# 010_SoC_RGMII_GBE_PHY.net
KiCad netlist of a schematic drawn in Altium Designer
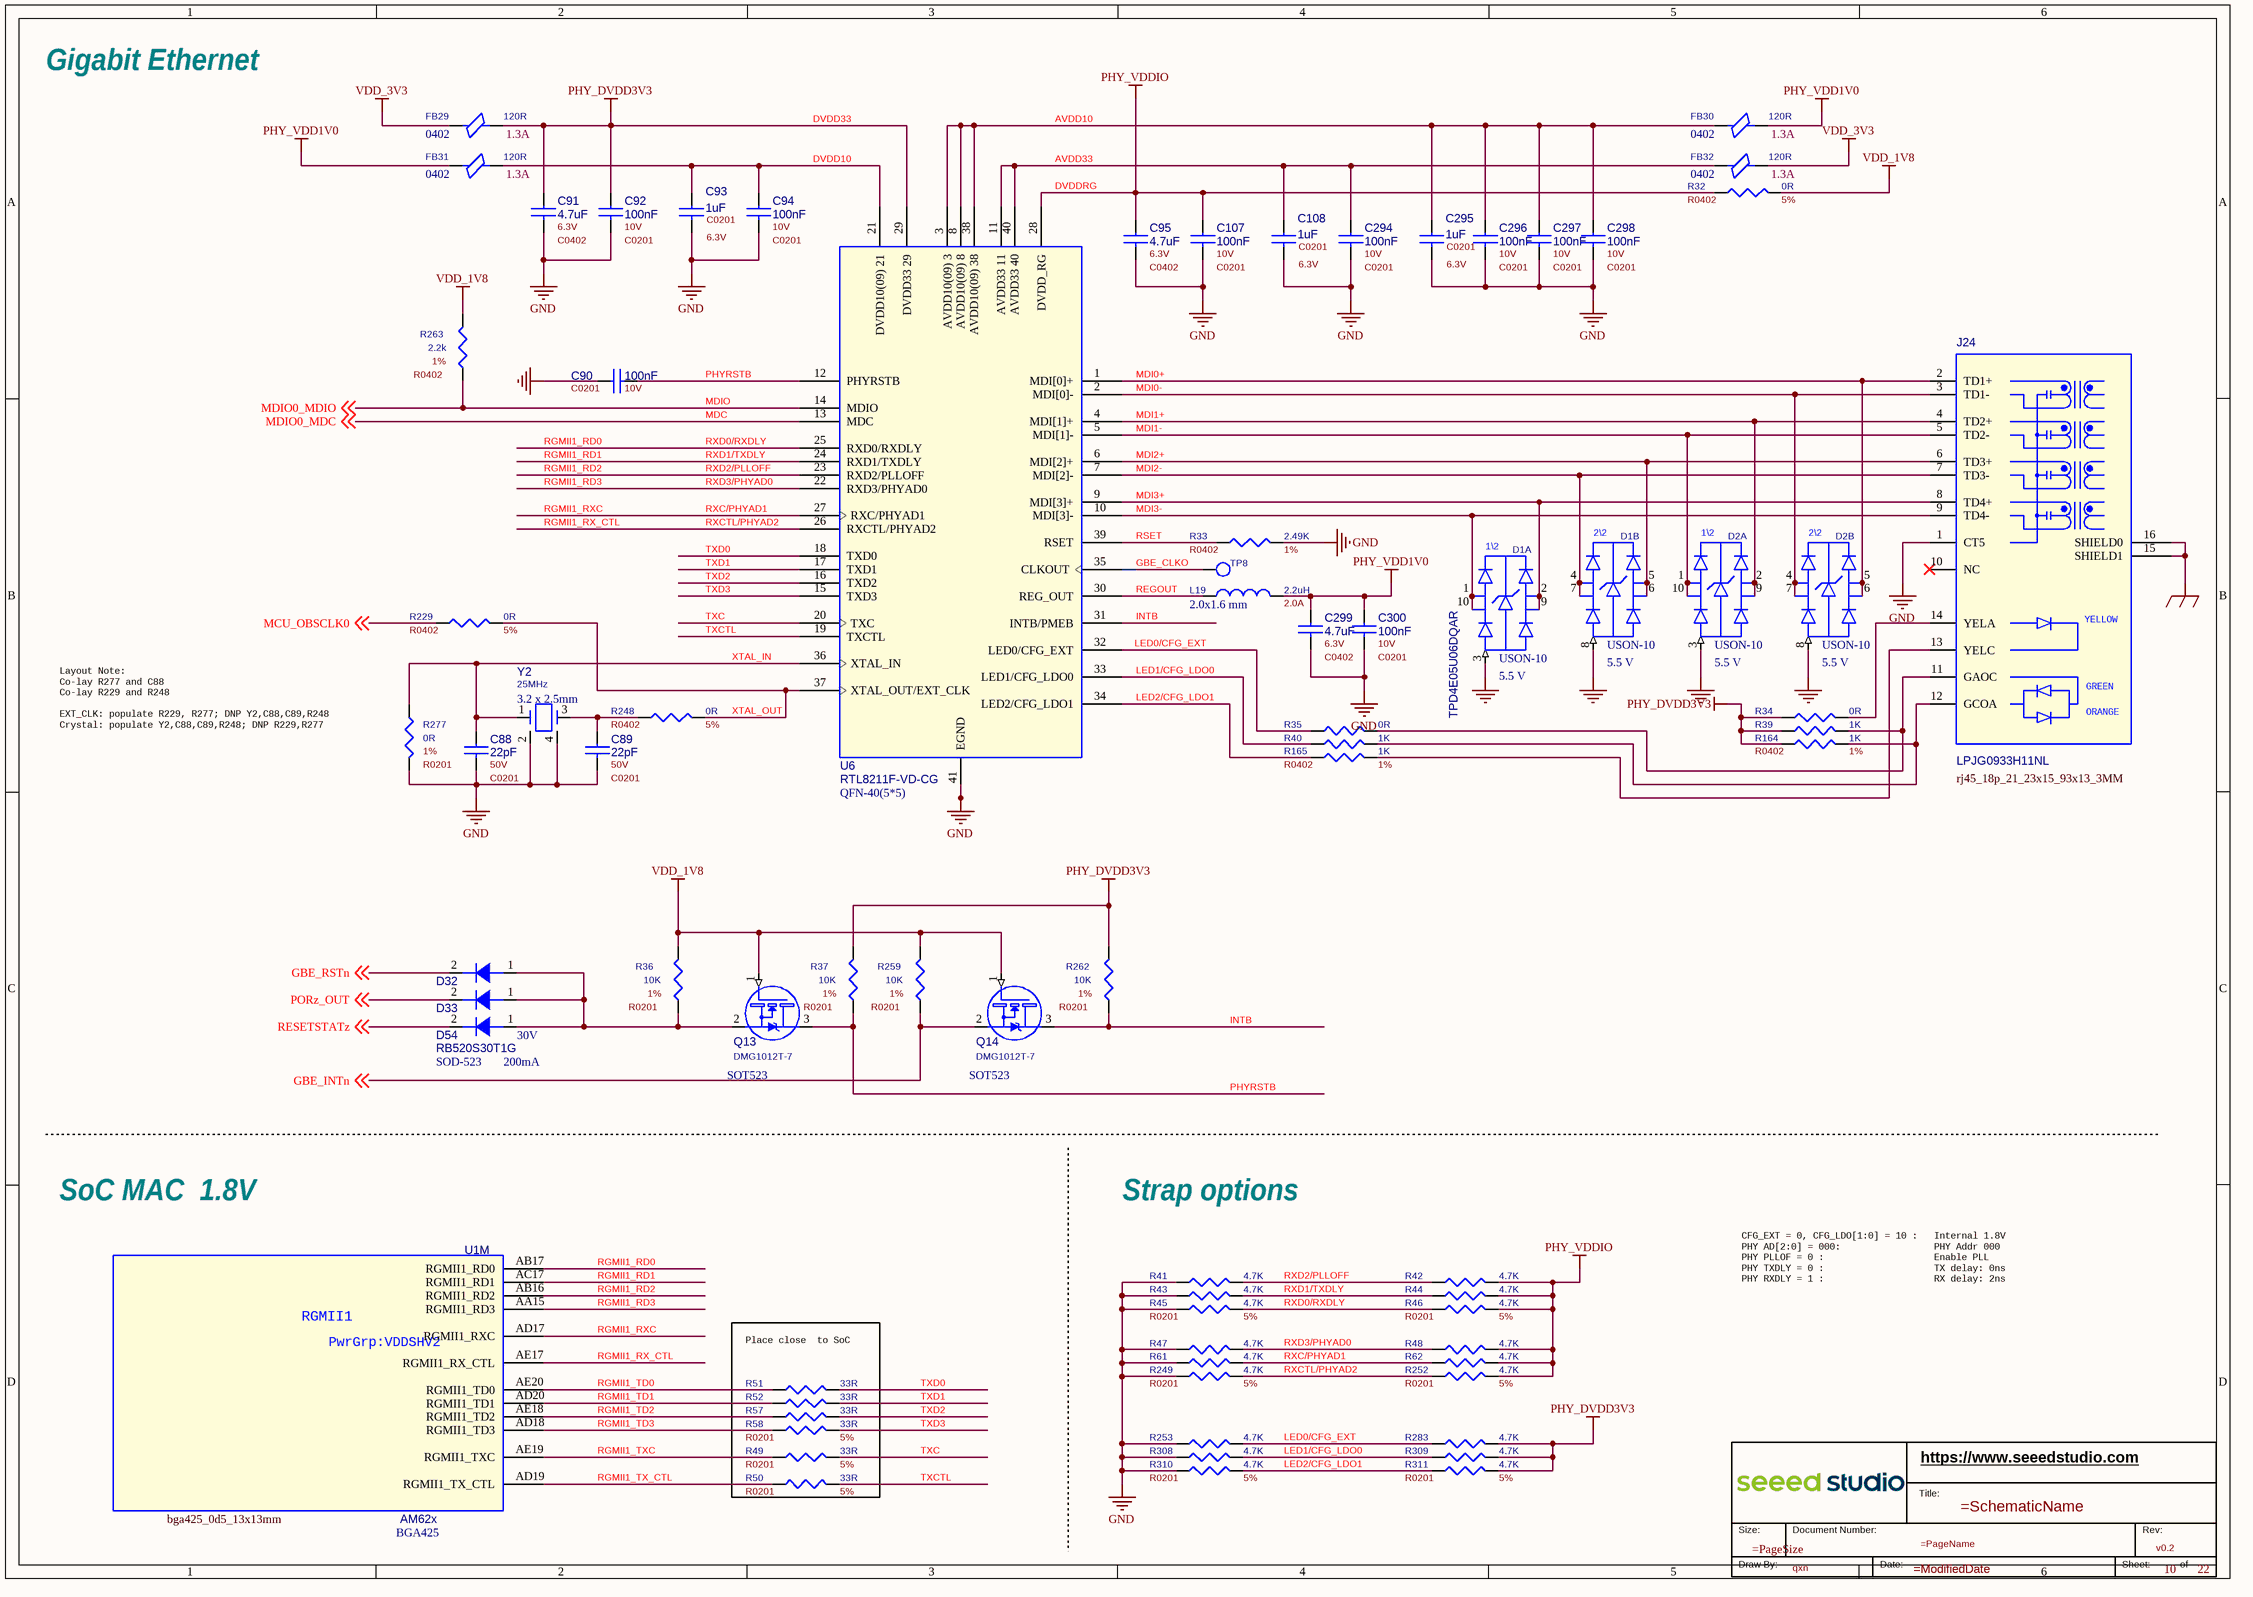
[diagram p0: 010_SoC RGMII & GBE PHY.SchDoc]

(export (version "E")
  (design (tool "Eeschema 10.0.6"))
  (components
    (comp (ref "C88")
      (value "22pF")
      (footprint "C0201")
      (description "CAP, Ceramic, SMD, 22pF, 5%, 50V, 0201")
      (fields
        (field (name "RATING") "50V")
        (field (name "PCB FOOTPRINT") "C0201")
        (field (name "TOLERANCE") "5%")
        (field (name "MANUFACTURER") "YAGEO")
      )
      (libsource (lib "*") (part "CC"))
    )
    (comp (ref "C89")
      (value "22pF")
      (footprint "C0201")
      (description "CAP, Ceramic, SMD, 22pF, 5%, 50V, 0201")
      (fields
        (field (name "RATING") "50V")
        (field (name "PCB FOOTPRINT") "C0201")
        (field (name "MANUFACTURER") "YAGEO")
        (field (name "TOLERANCE") "5%")
      )
      (libsource (lib "*") (part "CC"))
    )
    (comp (ref "C90")
      (value "100nF")
      (footprint "C0201")
      (description "CAP, Ceramic, SMD, 100nF, 10%, 10V, 0201")
      (fields
        (field (name "RATING") "10V")
        (field (name "PCB FOOTPRINT") "C0201")
        (field (name "MANUFACTURER") "YAGEO")
        (field (name "TOLERANCE") "10%")
      )
      (libsource (lib "") (part "CC_1"))
    )
    (comp (ref "C91")
      (value "4.7uF")
      (footprint "C0402")
      (description "CAP, Ceramic, SMD, 4.7uF, 20%, 6.3V, 0402")
      (fields
        (field (name "RATING") "6.3V")
        (field (name "PCB FOOTPRINT") "C0402")
        (field (name "TOLERANCE") "20%")
        (field (name "MANUFACTURER") "YAGEO")
      )
      (libsource (lib "*") (part "CC"))
    )
    (comp (ref "C92")
      (value "100nF")
      (footprint "C0201")
      (description "CAP, Ceramic, SMD, 100nF, 10%, 10V, 0201")
      (fields
        (field (name "RATING") "10V")
        (field (name "PCB FOOTPRINT") "C0201")
        (field (name "MANUFACTURER") "YAGEO")
        (field (name "TOLERANCE") "10%")
      )
      (libsource (lib "*") (part "CC"))
    )
    (comp (ref "C93")
      (value "1uF")
      (footprint "C0201")
      (description "CAP, Ceramic, SMD, 1uF, 20%, 6.3V, 0201")
      (fields
        (field (name "RATING") "6.3V")
        (field (name "PCB FOOTPRINT") "C0201")
        (field (name "TOLERANCE") "20%")
        (field (name "MANUFACTURER") "YAGEO")
      )
      (libsource (lib "*") (part "CC"))
    )
    (comp (ref "C94")
      (value "100nF")
      (footprint "C0201")
      (description "CAP, Ceramic, SMD, 100nF, 10%, 10V, 0201")
      (fields
        (field (name "RATING") "10V")
        (field (name "PCB FOOTPRINT") "C0201")
        (field (name "TOLERANCE") "10%")
        (field (name "MANUFACTURER") "YAGEO")
      )
      (libsource (lib "*") (part "CC"))
    )
    (comp (ref "C95")
      (value "4.7uF")
      (footprint "C0402")
      (description "CAP, Ceramic, SMD, 4.7uF, 20%, 6.3V, 0402")
      (fields
        (field (name "RATING") "6.3V")
        (field (name "PCB FOOTPRINT") "C0402")
        (field (name "TOLERANCE") "20%")
        (field (name "MANUFACTURER") "YAGEO")
      )
      (libsource (lib "*") (part "CC"))
    )
    (comp (ref "C107")
      (value "100nF")
      (footprint "C0201")
      (description "CAP, Ceramic, SMD, 100nF, 10%, 10V, 0201")
      (fields
        (field (name "RATING") "10V")
        (field (name "PCB FOOTPRINT") "C0201")
        (field (name "MANUFACTURER") "YAGEO")
        (field (name "TOLERANCE") "10%")
      )
      (libsource (lib "*") (part "CC"))
    )
    (comp (ref "C108")
      (value "1uF")
      (footprint "C0201")
      (description "CAP, Ceramic, SMD, 1uF, 20%, 6.3V, 0201")
      (fields
        (field (name "RATING") "6.3V")
        (field (name "PCB FOOTPRINT") "C0201")
        (field (name "MANUFACTURER") "YAGEO")
        (field (name "TOLERANCE") "20%")
      )
      (libsource (lib "*") (part "CC"))
    )
    (comp (ref "C294")
      (value "100nF")
      (footprint "C0201")
      (description "CAP, Ceramic, SMD, 100nF, 10%, 10V, 0201")
      (fields
        (field (name "RATING") "10V")
        (field (name "PCB FOOTPRINT") "C0201")
        (field (name "MANUFACTURER") "YAGEO")
        (field (name "TOLERANCE") "10%")
      )
      (libsource (lib "*") (part "CC"))
    )
    (comp (ref "C295")
      (value "1uF")
      (footprint "C0201")
      (description "CAP, Ceramic, SMD, 1uF, 20%, 6.3V, 0201")
      (fields
        (field (name "RATING") "6.3V")
        (field (name "PCB FOOTPRINT") "C0201")
        (field (name "MANUFACTURER") "YAGEO")
        (field (name "TOLERANCE") "20%")
      )
      (libsource (lib "*") (part "CC"))
    )
    (comp (ref "C296")
      (value "100nF")
      (footprint "C0201")
      (description "CAP, Ceramic, SMD, 100nF, 10%, 10V, 0201")
      (fields
        (field (name "RATING") "10V")
        (field (name "PCB FOOTPRINT") "C0201")
        (field (name "TOLERANCE") "10%")
        (field (name "MANUFACTURER") "YAGEO")
      )
      (libsource (lib "*") (part "CC"))
    )
    (comp (ref "C297")
      (value "100nF")
      (footprint "C0201")
      (description "CAP, Ceramic, SMD, 100nF, 10%, 10V, 0201")
      (fields
        (field (name "RATING") "10V")
        (field (name "PCB FOOTPRINT") "C0201")
        (field (name "TOLERANCE") "10%")
        (field (name "MANUFACTURER") "YAGEO")
      )
      (libsource (lib "*") (part "CC"))
    )
    (comp (ref "C298")
      (value "100nF")
      (footprint "C0201")
      (description "CAP, Ceramic, SMD, 100nF, 10%, 10V, 0201")
      (fields
        (field (name "RATING") "10V")
        (field (name "PCB FOOTPRINT") "C0201")
        (field (name "TOLERANCE") "10%")
        (field (name "MANUFACTURER") "YAGEO")
      )
      (libsource (lib "*") (part "CC"))
    )
    (comp (ref "C299")
      (value "4.7uF")
      (footprint "C0402")
      (description "CAP, Ceramic, SMD, 4.7uF, 20%, 6.3V, 0402")
      (fields
        (field (name "RATING") "6.3V")
        (field (name "PCB FOOTPRINT") "C0402")
        (field (name "MANUFACTURER") "YAGEO")
        (field (name "TOLERANCE") "20%")
      )
      (libsource (lib "*") (part "CC"))
    )
    (comp (ref "C300")
      (value "100nF")
      (footprint "C0201")
      (description "CAP, Ceramic, SMD, 100nF, 10%, 10V, 0201")
      (fields
        (field (name "RATING") "10V")
        (field (name "PCB FOOTPRINT") "C0201")
        (field (name "MANUFACTURER") "YAGEO")
        (field (name "TOLERANCE") "10%")
      )
      (libsource (lib "*") (part "CC"))
    )
    (comp (ref "D1")
      (value "D_ESD_DIFFPAIR")
      (footprint "uson10_0d5_2d5x1x0d5mm")
      (description "DIO, ESD, TPD4E05U06DQAR, --, 5.5 V, --, USON-10")
      (fields
        (field (name "PACKAGE SIZE") "USON-10")
        (field (name "RATED VOLTAGE") "5.5 V")
        (field (name "MANUFACTURER") "TI")
        (field (name "Comment") "D_ESD_DIFFPAIR")
      )
      (libsource (lib "*") (part "D_ESD_DIFFPAIR"))
    )
    (comp (ref "D2")
      (value "D_ESD_DIFFPAIR")
      (footprint "uson10_0d5_2d5x1x0d5mm")
      (description "DIO, ESD, TPD4E05U06DQAR, --, 5.5 V, --, USON-10")
      (fields
        (field (name "MANUFACTURER") "TI")
        (field (name "RATED VOLTAGE") "5.5 V")
        (field (name "PACKAGE SIZE") "USON-10")
      )
      (libsource (lib "*") (part "D_ESD_DIFFPAIR"))
    )
    (comp (ref "D32")
      (value "D")
      (footprint "sod_523")
      (description "DIO, Schottky, RB520S30T1G, , , , SOD-523")
      (fields (field (name "MANUFACTURER") "ON"))
      (libsource (lib "*") (part "D"))
    )
    (comp (ref "D33")
      (value "D")
      (footprint "sod_523")
      (description "DIO, Schottky, RB520S30T1G, , , , SOD-523")
      (fields (field (name "MANUFACTURER") "ON"))
      (libsource (lib "*") (part "D"))
    )
    (comp (ref "D54")
      (value "RB520S30T1G")
      (footprint "sod_523")
      (description "DIO, Schottky, RB520S30T1G, , , , SOD-523")
      (fields
        (field (name "MANUFACTURER") "ON")
        (field (name "REPETITIVE REVERSE VOLTAGE MAXIMUM") "30V")
        (field (name "PEAK FORWARD CURRENT") "200mA")
        (field (name "PACKAGE SIZE") "SOD-523")
        (field (name "Comment") "D")
      )
      (libsource (lib "*") (part "D"))
    )
    (comp (ref "FB29")
      (value "120R")
      (footprint "L0402")
      (description "Ferrite Bead, 120R, , 1.3A, 0402")
      (fields
        (field (name "RATING") "1.3A")
        (field (name "PACKAGE SIZE") "0402")
        (field (name "MANUFACTURER") "Murata")
        (field (name "Comment") "FB")
      )
      (libsource (lib "*") (part "FB"))
    )
    (comp (ref "FB30")
      (value "120R")
      (footprint "L0402")
      (description "Ferrite Bead, 120R, , 1.3A, 0402")
      (fields
        (field (name "RATING") "1.3A")
        (field (name "MANUFACTURER") "Murata")
        (field (name "PACKAGE SIZE") "0402")
        (field (name "Comment") "FB")
      )
      (libsource (lib "*") (part "FB"))
    )
    (comp (ref "FB31")
      (value "120R")
      (footprint "L0402")
      (description "Ferrite Bead, 120R, , 1.3A, 0402")
      (fields
        (field (name "RATING") "1.3A")
        (field (name "MANUFACTURER") "Murata")
        (field (name "PACKAGE SIZE") "0402")
        (field (name "Comment") "FB")
      )
      (libsource (lib "*") (part "FB"))
    )
    (comp (ref "FB32")
      (value "120R")
      (footprint "L0402")
      (description "Ferrite Bead, 120R, , 1.3A, 0402")
      (fields
        (field (name "RATING") "1.3A")
        (field (name "PACKAGE SIZE") "0402")
        (field (name "MANUFACTURER") "Murata")
        (field (name "Comment") "FB")
      )
      (libsource (lib "*") (part "FB"))
    )
    (comp (ref "J24")
      (value "LPJG0933H11NL")
      (footprint "rj45_18p_21_23x15_93x13_3MM")
      (description "CONN, RJ45, LPJG0933H11NL, 16P, DIP")
      (fields
        (field (name "PCB FOOTPRINT") "rj45_18p_21_23x15_93x13_3MM")
        (field (name "MANUFACTURER") "LINK-PP")
        (field (name "Comment") "RJ45_LPJG0933H11NL")
      )
      (libsource (lib "*") (part "RJ45_LPJG0933H11NL"))
    )
    (comp (ref "L19")
      (value "2.2uH")
      (footprint "L2016")
      (description "Power Inductor, 2.2uH, 20%, 2.0A, 2.0x1.6 mm")
      (fields
        (field (name "RATING") "2.0A")
        (field (name "MANUFACTURER") "CODACA")
        (field (name "PACKAGE SIZE") "2.0x1.6 mm")
        (field (name "Comment") "L")
      )
      (libsource (lib "*") (part "L"))
    )
    (comp (ref "Q13")
      (value "DMG1012T-7")
      (footprint "SOT_523")
      (description "XSTR, MOSFET, N-Channel, DMG1012T-7, 20V, 630mA, SOT523, SMD")
      (fields
        (field (name "PACKAGE SIZE") "SOT523")
        (field (name "MANUFACTURER") "Diodes")
        (field (name "Comment") "NMOS_123")
      )
      (libsource (lib "*") (part "NMOS_123"))
    )
    (comp (ref "Q14")
      (value "DMG1012T-7")
      (footprint "SOT_523")
      (description "XSTR, MOSFET, N-Channel, DMG1012T-7, 20V, 630mA, SOT523, SMD")
      (fields
        (field (name "PACKAGE SIZE") "SOT523")
        (field (name "MANUFACTURER") "Diodes")
        (field (name "Comment") "NMOS_123")
      )
      (libsource (lib "*") (part "NMOS_123"))
    )
    (comp (ref "R32")
      (value "0R")
      (footprint "R0402")
      (description "RES, Thick Film, 0R, 5%, 1/16W, SMD, 0402")
      (fields
        (field (name "RATING") "5%")
        (field (name "PCB FOOTPRINT") "R0402")
        (field (name "MANUFACTURER") "YAGEO")
        (field (name "Comment") "R")
      )
      (libsource (lib "*") (part "R"))
    )
    (comp (ref "R33")
      (value "2.49K")
      (footprint "R0402")
      (description "RES, Thick Film, 2.49K, 1%, 1/16W, SMD, 0402")
      (fields
        (field (name "RATING") "1%")
        (field (name "PCB FOOTPRINT") "R0402")
        (field (name "MANUFACTURER") "YAGEO")
        (field (name "Comment") "R")
      )
      (libsource (lib "*") (part "R"))
    )
    (comp (ref "R34")
      (value "0R")
      (footprint "R0402")
      (description "RES, Thick Film, 0R, 5%, 1/16W, SMD, 0402")
      (fields (field (name "MANUFACTURER") "YAGEO") (field (name "Comment") "R"))
      (libsource (lib "*") (part "R"))
    )
    (comp (ref "R35")
      (value "0R")
      (footprint "R0402")
      (description "RES, Thick Film, 0R, 5%, 1/16W, SMD, 0402")
      (fields (field (name "MANUFACTURER") "YAGEO") (field (name "Comment") "R"))
      (libsource (lib "*") (part "R"))
    )
    (comp (ref "R36")
      (value "10K")
      (footprint "R0201")
      (description "RES, Thick Film, 10K, 1%, 1/20W, SMD, 0201")
      (fields
        (field (name "RATING") "1%")
        (field (name "PCB FOOTPRINT") "R0201")
        (field (name "MANUFACTURER") "YAGEO")
        (field (name "Comment") "R")
      )
      (libsource (lib "") (part "R_1"))
    )
    (comp (ref "R37")
      (value "10K")
      (footprint "R0201")
      (description "RES, Thick Film, 10K, 1%, 1/20W, SMD, 0201")
      (fields
        (field (name "RATING") "1%")
        (field (name "PCB FOOTPRINT") "R0201")
        (field (name "MANUFACTURER") "YAGEO")
        (field (name "Comment") "R")
      )
      (libsource (lib "") (part "R_1"))
    )
    (comp (ref "R39")
      (value "1K")
      (footprint "R0402")
      (description "RES, Thick Film, 1K, 1%, 1/16W, SMD, 0402")
      (fields (field (name "MANUFACTURER") "YAGEO") (field (name "Comment") "R"))
      (libsource (lib "*") (part "R"))
    )
    (comp (ref "R40")
      (value "1K")
      (footprint "R0402")
      (description "RES, Thick Film, 1K, 1%, 1/16W, SMD, 0402")
      (fields (field (name "MANUFACTURER") "YAGEO") (field (name "Comment") "R"))
      (libsource (lib "*") (part "R"))
    )
    (comp (ref "R41")
      (value "4.7K")
      (footprint "R0201")
      (description "RES, Thick Film, 4.7K, 5%, 1/20W, SMD, 0201")
      (fields (field (name "MANUFACTURER") "YAGEO") (field (name "Comment") "R"))
      (libsource (lib "*") (part "R"))
    )
    (comp (ref "R42")
      (value "4.7K")
      (footprint "R0201")
      (description "RES, Thick Film, 4.7K, 5%, 1/20W, SMD, 0201")
      (fields (field (name "MANUFACTURER") "YAGEO") (field (name "Comment") "R"))
      (libsource (lib "*") (part "R"))
    )
    (comp (ref "R43")
      (value "4.7K")
      (footprint "R0201")
      (description "RES, Thick Film, 4.7K, 5%, 1/20W, SMD, 0201")
      (fields (field (name "MANUFACTURER") "YAGEO") (field (name "Comment") "R"))
      (libsource (lib "*") (part "R"))
    )
    (comp (ref "R44")
      (value "4.7K")
      (footprint "R0201")
      (description "RES, Thick Film, 4.7K, 5%, 1/20W, SMD, 0201")
      (fields (field (name "MANUFACTURER") "YAGEO") (field (name "Comment") "R"))
      (libsource (lib "*") (part "R"))
    )
    (comp (ref "R45")
      (value "4.7K")
      (footprint "R0201")
      (description "RES, Thick Film, 4.7K, 5%, 1/20W, SMD, 0201")
      (fields
        (field (name "RATING") "5%")
        (field (name "PCB FOOTPRINT") "R0201")
        (field (name "MANUFACTURER") "YAGEO")
        (field (name "Comment") "R")
      )
      (libsource (lib "*") (part "R"))
    )
    (comp (ref "R46")
      (value "4.7K")
      (footprint "R0201")
      (description "RES, Thick Film, 4.7K, 5%, 1/20W, SMD, 0201")
      (fields
        (field (name "RATING") "5%")
        (field (name "PCB FOOTPRINT") "R0201")
        (field (name "MANUFACTURER") "YAGEO")
        (field (name "Comment") "R")
      )
      (libsource (lib "*") (part "R"))
    )
    (comp (ref "R47")
      (value "4.7K")
      (footprint "R0201")
      (description "RES, Thick Film, 4.7K, 5%, 1/20W, SMD, 0201")
      (fields (field (name "MANUFACTURER") "YAGEO") (field (name "Comment") "R"))
      (libsource (lib "*") (part "R"))
    )
    (comp (ref "R48")
      (value "4.7K")
      (footprint "R0201")
      (description "RES, Thick Film, 4.7K, 5%, 1/20W, SMD, 0201")
      (fields (field (name "MANUFACTURER") "YAGEO") (field (name "Comment") "R"))
      (libsource (lib "*") (part "R"))
    )
    (comp (ref "R49")
      (value "33R")
      (footprint "R0201")
      (description "RES, Thick Film, 33R, 5%, 1/20W, SMD, 0201")
      (fields
        (field (name "RATING") "5%")
        (field (name "PCB FOOTPRINT") "R0201")
        (field (name "MANUFACTURER") "YAGEO")
        (field (name "Comment") "R")
      )
      (libsource (lib "*") (part "R"))
    )
    (comp (ref "R50")
      (value "33R")
      (footprint "R0201")
      (description "RES, Thick Film, 33R, 5%, 1/20W, SMD, 0201")
      (fields
        (field (name "RATING") "5%")
        (field (name "PCB FOOTPRINT") "R0201")
        (field (name "MANUFACTURER") "YAGEO")
        (field (name "Comment") "R")
      )
      (libsource (lib "*") (part "R"))
    )
    (comp (ref "R51")
      (value "33R")
      (footprint "R0201")
      (description "RES, Thick Film, 33R, 5%, 1/20W, SMD, 0201")
      (fields (field (name "MANUFACTURER") "YAGEO") (field (name "Comment") "R"))
      (libsource (lib "*") (part "R"))
    )
    (comp (ref "R52")
      (value "33R")
      (footprint "R0201")
      (description "RES, Thick Film, 33R, 5%, 1/20W, SMD, 0201")
      (fields (field (name "MANUFACTURER") "YAGEO") (field (name "Comment") "R"))
      (libsource (lib "*") (part "R"))
    )
    (comp (ref "R57")
      (value "33R")
      (footprint "R0201")
      (description "RES, Thick Film, 33R, 5%, 1/20W, SMD, 0201")
      (fields (field (name "MANUFACTURER") "YAGEO") (field (name "Comment") "R"))
      (libsource (lib "*") (part "R"))
    )
    (comp (ref "R58")
      (value "33R")
      (footprint "R0201")
      (description "RES, Thick Film, 33R, 5%, 1/20W, SMD, 0201")
      (fields
        (field (name "RATING") "5%")
        (field (name "PCB FOOTPRINT") "R0201")
        (field (name "MANUFACTURER") "YAGEO")
        (field (name "Comment") "R")
      )
      (libsource (lib "*") (part "R"))
    )
    (comp (ref "R61")
      (value "4.7K")
      (footprint "R0201")
      (description "RES, Thick Film, 4.7K, 5%, 1/20W, SMD, 0201")
      (fields (field (name "MANUFACTURER") "YAGEO") (field (name "Comment") "R"))
      (libsource (lib "*") (part "R"))
    )
    (comp (ref "R62")
      (value "4.7K")
      (footprint "R0201")
      (description "RES, Thick Film, 4.7K, 5%, 1/20W, SMD, 0201")
      (fields (field (name "MANUFACTURER") "YAGEO") (field (name "Comment") "R"))
      (libsource (lib "*") (part "R"))
    )
    (comp (ref "R164")
      (value "1K")
      (footprint "R0402")
      (description "RES, Thick Film, 1K, 1%, 1/16W, SMD, 0402")
      (fields
        (field (name "RATING") "1%")
        (field (name "PCB FOOTPRINT") "R0402")
        (field (name "MANUFACTURER") "YAGEO")
        (field (name "Comment") "R")
      )
      (libsource (lib "*") (part "R"))
    )
    (comp (ref "R165")
      (value "1K")
      (footprint "R0402")
      (description "RES, Thick Film, 1K, 1%, 1/16W, SMD, 0402")
      (fields
        (field (name "RATING") "1%")
        (field (name "PCB FOOTPRINT") "R0402")
        (field (name "MANUFACTURER") "YAGEO")
        (field (name "Comment") "R")
      )
      (libsource (lib "*") (part "R"))
    )
    (comp (ref "R229")
      (value "0R")
      (footprint "R0402")
      (description "RES, Thick Film, 0R, 5%, 1/16W, SMD, 0402")
      (fields
        (field (name "RATING") "5%")
        (field (name "PCB FOOTPRINT") "R0402")
        (field (name "MANUFACTURER") "YAGEO")
        (field (name "Comment") "R")
      )
      (libsource (lib "*") (part "R"))
    )
    (comp (ref "R248")
      (value "0R")
      (footprint "R0402")
      (description "RES, Thick Film, 0R, 5%, 1/16W, SMD, 0402")
      (fields
        (field (name "RATING") "5%")
        (field (name "PCB FOOTPRINT") "R0402")
        (field (name "MANUFACTURER") "YAGEO")
        (field (name "Comment") "R")
      )
      (libsource (lib "*") (part "R"))
    )
    (comp (ref "R249")
      (value "4.7K")
      (footprint "R0201")
      (description "RES, Thick Film, 4.7K, 5%, 1/20W, SMD, 0201")
      (fields
        (field (name "RATING") "5%")
        (field (name "PCB FOOTPRINT") "R0201")
        (field (name "MANUFACTURER") "YAGEO")
        (field (name "Comment") "R")
      )
      (libsource (lib "*") (part "R"))
    )
    (comp (ref "R252")
      (value "4.7K")
      (footprint "R0201")
      (description "RES, Thick Film, 4.7K, 5%, 1/20W, SMD, 0201")
      (fields
        (field (name "RATING") "5%")
        (field (name "PCB FOOTPRINT") "R0201")
        (field (name "MANUFACTURER") "YAGEO")
        (field (name "Comment") "R")
      )
      (libsource (lib "*") (part "R"))
    )
    (comp (ref "R253")
      (value "4.7K")
      (footprint "R0201")
      (description "RES, Thick Film, 4.7K, 5%, 1/20W, SMD, 0201")
      (fields (field (name "MANUFACTURER") "YAGEO") (field (name "Comment") "R"))
      (libsource (lib "*") (part "R"))
    )
    (comp (ref "R259")
      (value "10K")
      (footprint "R0201")
      (description "RES, Thick Film, 10K, 1%, 1/20W, SMD, 0201")
      (fields
        (field (name "RATING") "1%")
        (field (name "PCB FOOTPRINT") "R0201")
        (field (name "MANUFACTURER") "YAGEO")
        (field (name "Comment") "R")
      )
      (libsource (lib "") (part "R_1"))
    )
    (comp (ref "R262")
      (value "10K")
      (footprint "R0201")
      (description "RES, Thick Film, 10K, 1%, 1/20W, SMD, 0201")
      (fields
        (field (name "RATING") "1%")
        (field (name "PCB FOOTPRINT") "R0201")
        (field (name "MANUFACTURER") "YAGEO")
        (field (name "Comment") "R")
      )
      (libsource (lib "") (part "R_1"))
    )
    (comp (ref "R263")
      (value "2.2k")
      (footprint "R0402")
      (description "RES, Thick Film, 2.2k, 1%, 1/16W, SMD, 0402")
      (fields
        (field (name "RATING") "1%")
        (field (name "PCB FOOTPRINT") "R0402")
        (field (name "MANUFACTURER") "YAGEO")
        (field (name "Comment") "R")
      )
      (libsource (lib "") (part "R_1"))
    )
    (comp (ref "R277")
      (value "0R")
      (footprint "R0201")
      (description "RES, Thick Film, 0R, 5%, 1/20W, SMD, 0201")
      (fields
        (field (name "RATING") "1%")
        (field (name "PCB FOOTPRINT") "R0201")
        (field (name "MANUFACTURER") "YAGEO")
        (field (name "Comment") "R")
      )
      (libsource (lib "") (part "R_1"))
    )
    (comp (ref "R283")
      (value "4.7K")
      (footprint "R0201")
      (description "RES, Thick Film, 4.7K, 5%, 1/20W, SMD, 0201")
      (fields (field (name "MANUFACTURER") "YAGEO") (field (name "Comment") "R"))
      (libsource (lib "*") (part "R"))
    )
    (comp (ref "R308")
      (value "4.7K")
      (footprint "R0201")
      (description "RES, Thick Film, 4.7K, 5%, 1/20W, SMD, 0201")
      (fields (field (name "MANUFACTURER") "YAGEO") (field (name "Comment") "R"))
      (libsource (lib "*") (part "R"))
    )
    (comp (ref "R309")
      (value "4.7K")
      (footprint "R0201")
      (description "RES, Thick Film, 4.7K, 5%, 1/20W, SMD, 0201")
      (fields (field (name "MANUFACTURER") "YAGEO") (field (name "Comment") "R"))
      (libsource (lib "*") (part "R"))
    )
    (comp (ref "R310")
      (value "4.7K")
      (footprint "R0201")
      (description "RES, Thick Film, 4.7K, 5%, 1/20W, SMD, 0201")
      (fields
        (field (name "RATING") "5%")
        (field (name "PCB FOOTPRINT") "R0201")
        (field (name "MANUFACTURER") "YAGEO")
        (field (name "Comment") "R")
      )
      (libsource (lib "*") (part "R"))
    )
    (comp (ref "R311")
      (value "4.7K")
      (footprint "R0201")
      (description "RES, Thick Film, 4.7K, 5%, 1/20W, SMD, 0201")
      (fields
        (field (name "RATING") "5%")
        (field (name "PCB FOOTPRINT") "R0201")
        (field (name "MANUFACTURER") "YAGEO")
        (field (name "Comment") "R")
      )
      (libsource (lib "*") (part "R"))
    )
    (comp (ref "TP8")
      (value "Test Point")
      (footprint "tp1-8040")
      (description "MISC, Test Point, Test Point, SMD, TP30C_SMD")
      (libsource (lib "*") (part "Test Point"))
    )
    (comp (ref "U1")
      (value "AM62x")
      (footprint "bga425_0d5_13x13mm")
      (description "IC, Controller, MPU, AM62x, BGA425")
      (fields
        (field (name "PCB FOOTPRINT") "bga425_0d5_13x13mm")
        (field (name "PACKAGE SIZE") "BGA425")
        (field (name "MANUFACTURER") "TI")
        (field (name "Comment") "AM62x_BGA425")
      )
      (libsource (lib "*") (part "AM62x_BGA425"))
    )
    (comp (ref "U6")
      (value "RTL8211F-VD-CG")
      (footprint "qfn40_0D4_5x5mm")
      (description "IC, Interface, Ethernet, RTL8211F-VD-CG, QFN-40(5*5)")
      (fields
        (field (name "MANUFACTURER") "Realtek")
        (field (name "PACKAGE SIZE") "QFN-40(5*5)")
        (field (name "Comment") "RTL8211")
      )
      (libsource (lib "*") (part "RTL8211"))
    )
    (comp (ref "Y2")
      (value "25MHz")
      (footprint "CRY-SMD4-CX101F")
      (description "Crystal, SMD, 25MHz, 20 ppm, 18pF")
      (fields
        (field (name "MANUFACTURER") "Interquip")
        (field (name "PACKAGE SIZE") "3.2 x 2.5mm")
        (field (name "Comment") "XTAL_4P_2")
      )
      (libsource (lib "*") (part "XTAL_4P_2"))
    )
  )
  (nets
    (net (code "1") (name "/AVDD10") (class "Default")
      (node (ref "C295") (pin "1") (pinfunction "1_1") (pintype "passive"))
      (node (ref "C296") (pin "1") (pinfunction "1_1") (pintype "passive"))
      (node (ref "C297") (pin "1") (pinfunction "1_1") (pintype "passive"))
      (node (ref "C298") (pin "1") (pinfunction "1_1") (pintype "passive"))
      (node (ref "FB30") (pin "1") (pinfunction "1_1") (pintype "passive"))
      (node (ref "U6") (pin "3") (pinfunction "AVDD10(09)_3_3") (pintype "power_in"))
      (node (ref "U6") (pin "38") (pinfunction "AVDD10(09)_38_38") (pintype "power_in"))
      (node (ref "U6") (pin "8") (pinfunction "AVDD10(09)_8_8") (pintype "power_in"))
    )
    (net (code "2") (name "/AVDD33") (class "Default")
      (node (ref "C108") (pin "1") (pinfunction "1_1") (pintype "passive"))
      (node (ref "C294") (pin "1") (pinfunction "1_1") (pintype "passive"))
      (node (ref "FB32") (pin "1") (pinfunction "1_1") (pintype "passive"))
      (node (ref "U6") (pin "11") (pinfunction "AVDD33_11_11") (pintype "power_in"))
      (node (ref "U6") (pin "40") (pinfunction "AVDD33_40_40") (pintype "power_in"))
    )
    (net (code "3") (name "/DVDD10") (class "Default")
      (node (ref "C93") (pin "1") (pinfunction "1_1") (pintype "passive"))
      (node (ref "C94") (pin "1") (pinfunction "1_1") (pintype "passive"))
      (node (ref "FB31") (pin "2") (pinfunction "2_2") (pintype "passive"))
      (node (ref "U6") (pin "21") (pinfunction "DVDD10(09)_21_21") (pintype "power_in"))
    )
    (net (code "4") (name "/GBE_CLKO") (class "Default")
      (node (ref "TP8") (pin "1") (pinfunction "TP_1") (pintype "passive"))
      (node (ref "U6") (pin "35") (pinfunction "CLKOUT_35") (pintype "passive"))
    )
    (net (code "5") (name "/INTB") (class "Default")
      (node (ref "Q14") (pin "3") (pinfunction "D_3") (pintype "passive"))
      (node (ref "R262") (pin "2") (pinfunction "2_2") (pintype "passive"))
      (node (ref "U6") (pin "31") (pinfunction "INTB/PMEB_31") (pintype "passive"))
    )
    (net (code "6") (name "/LED0{slash}CFG_EXT") (class "Default")
      (node (ref "R253") (pin "2") (pinfunction "2_2") (pintype "passive"))
      (node (ref "R283") (pin "1") (pinfunction "1_1") (pintype "passive"))
      (node (ref "R35") (pin "1") (pinfunction "1_1") (pintype "passive"))
      (node (ref "U6") (pin "32") (pinfunction "LED0/CFG_EXT_32") (pintype "passive"))
    )
    (net (code "7") (name "/LED1{slash}CFG_LDO0") (class "Default")
      (node (ref "R308") (pin "2") (pinfunction "2_2") (pintype "passive"))
      (node (ref "R309") (pin "1") (pinfunction "1_1") (pintype "passive"))
      (node (ref "R40") (pin "1") (pinfunction "1_1") (pintype "passive"))
      (node (ref "U6") (pin "33") (pinfunction "LED1/CFG_LDO0_33") (pintype "passive"))
    )
    (net (code "8") (name "/LED2{slash}CFG_LDO1") (class "Default")
      (node (ref "R165") (pin "1") (pinfunction "1_1") (pintype "passive"))
      (node (ref "R310") (pin "2") (pinfunction "2_2") (pintype "passive"))
      (node (ref "R311") (pin "1") (pinfunction "1_1") (pintype "passive"))
      (node (ref "U6") (pin "34") (pinfunction "LED2/CFG_LDO1_34") (pintype "passive"))
    )
    (net (code "9") (name "/MDI0+") (class "Default")
      (node (ref "D2") (pin "5") (pinfunction "4A_5") (pintype "passive"))
      (node (ref "D2") (pin "6") (pinfunction "4B_6") (pintype "passive"))
      (node (ref "J24") (pin "2") (pinfunction "TD1+_2") (pintype "passive"))
      (node (ref "U6") (pin "1") (pinfunction "MDI[0]+_1") (pintype "passive"))
    )
    (net (code "10") (name "/MDI0-") (class "Default")
      (node (ref "D2") (pin "4") (pinfunction "3A_4") (pintype "passive"))
      (node (ref "D2") (pin "7") (pinfunction "3B_7") (pintype "passive"))
      (node (ref "J24") (pin "3") (pinfunction "TD1-_3") (pintype "passive"))
      (node (ref "U6") (pin "2") (pinfunction "MDI[0]-_2") (pintype "passive"))
    )
    (net (code "11") (name "/MDI1+") (class "Default")
      (node (ref "D2") (pin "2") (pinfunction "2A_2") (pintype "passive"))
      (node (ref "D2") (pin "9") (pinfunction "2B_9") (pintype "passive"))
      (node (ref "J24") (pin "4") (pinfunction "TD2+_4") (pintype "passive"))
      (node (ref "U6") (pin "4") (pinfunction "MDI[1]+_4") (pintype "passive"))
    )
    (net (code "12") (name "/MDI1-") (class "Default")
      (node (ref "D2") (pin "1") (pinfunction "1A_1") (pintype "passive"))
      (node (ref "D2") (pin "10") (pinfunction "1B_10") (pintype "passive"))
      (node (ref "J24") (pin "5") (pinfunction "TD2-_5") (pintype "passive"))
      (node (ref "U6") (pin "5") (pinfunction "MDI[1]-_5") (pintype "passive"))
    )
    (net (code "13") (name "/MDI2+") (class "Default")
      (node (ref "D1") (pin "5") (pinfunction "4A_5") (pintype "passive"))
      (node (ref "D1") (pin "6") (pinfunction "4B_6") (pintype "passive"))
      (node (ref "J24") (pin "6") (pinfunction "TD3+_6") (pintype "passive"))
      (node (ref "U6") (pin "6") (pinfunction "MDI[2]+_6") (pintype "passive"))
    )
    (net (code "14") (name "/MDI2-") (class "Default")
      (node (ref "D1") (pin "4") (pinfunction "3A_4") (pintype "passive"))
      (node (ref "D1") (pin "7") (pinfunction "3B_7") (pintype "passive"))
      (node (ref "J24") (pin "7") (pinfunction "TD3-_7") (pintype "passive"))
      (node (ref "U6") (pin "7") (pinfunction "MDI[2]-_7") (pintype "passive"))
    )
    (net (code "15") (name "/MDI3+") (class "Default")
      (node (ref "D1") (pin "2") (pinfunction "2A_2") (pintype "passive"))
      (node (ref "D1") (pin "9") (pinfunction "2B_9") (pintype "passive"))
      (node (ref "J24") (pin "8") (pinfunction "TD4+_8") (pintype "passive"))
      (node (ref "U6") (pin "9") (pinfunction "MDI[3]+_9") (pintype "passive"))
    )
    (net (code "16") (name "/MDI3-") (class "Default")
      (node (ref "D1") (pin "1") (pinfunction "1A_1") (pintype "passive"))
      (node (ref "D1") (pin "10") (pinfunction "1B_10") (pintype "passive"))
      (node (ref "J24") (pin "9") (pinfunction "TD4-_9") (pintype "passive"))
      (node (ref "U6") (pin "10") (pinfunction "MDI[3]-_10") (pintype "passive"))
    )
    (net (code "17") (name "/PHYRSTB") (class "Default")
      (node (ref "C90") (pin "2") (pinfunction "2_2") (pintype "passive"))
      (node (ref "Q13") (pin "3") (pinfunction "D_3") (pintype "passive"))
      (node (ref "R37") (pin "2") (pinfunction "2_2") (pintype "passive"))
      (node (ref "U6") (pin "12") (pinfunction "PHYRSTB_12") (pintype "passive"))
    )
    (net (code "18") (name "/REGOUT") (class "Default")
      (node (ref "L19") (pin "1") (pinfunction "1_1") (pintype "passive"))
      (node (ref "U6") (pin "30") (pinfunction "REG_OUT_30") (pintype "power_in"))
    )
    (net (code "19") (name "/RGMII1_RD0") (class "Default")
      (node (ref "R45") (pin "2") (pinfunction "2_2") (pintype "passive"))
      (node (ref "R46") (pin "1") (pinfunction "1_1") (pintype "passive"))
      (node (ref "U1") (pin "AB17") (pinfunction "RGMII1_RD0_AB17") (pintype "passive"))
      (node (ref "U6") (pin "25") (pinfunction "RXD0/RXDLY_25") (pintype "passive"))
    )
    (net (code "20") (name "/RGMII1_RD1") (class "Default")
      (node (ref "R43") (pin "2") (pinfunction "2_2") (pintype "passive"))
      (node (ref "R44") (pin "1") (pinfunction "1_1") (pintype "passive"))
      (node (ref "U1") (pin "AC17") (pinfunction "RGMII1_RD1_AC17") (pintype "passive"))
      (node (ref "U6") (pin "24") (pinfunction "RXD1/TXDLY_24") (pintype "passive"))
    )
    (net (code "21") (name "/RGMII1_RD2") (class "Default")
      (node (ref "R41") (pin "2") (pinfunction "2_2") (pintype "passive"))
      (node (ref "R42") (pin "1") (pinfunction "1_1") (pintype "passive"))
      (node (ref "U1") (pin "AB16") (pinfunction "RGMII1_RD2_AB16") (pintype "passive"))
      (node (ref "U6") (pin "23") (pinfunction "RXD2/PLLOFF_23") (pintype "passive"))
    )
    (net (code "22") (name "/RGMII1_RD3") (class "Default")
      (node (ref "R47") (pin "2") (pinfunction "2_2") (pintype "passive"))
      (node (ref "R48") (pin "1") (pinfunction "1_1") (pintype "passive"))
      (node (ref "U1") (pin "AA15") (pinfunction "RGMII1_RD3_AA15") (pintype "passive"))
      (node (ref "U6") (pin "22") (pinfunction "RXD3/PHYAD0_22") (pintype "passive"))
    )
    (net (code "23") (name "/RGMII1_RXC") (class "Default")
      (node (ref "R61") (pin "2") (pinfunction "2_2") (pintype "passive"))
      (node (ref "R62") (pin "1") (pinfunction "1_1") (pintype "passive"))
      (node (ref "U1") (pin "AD17") (pinfunction "RGMII1_RXC_AD17") (pintype "passive"))
      (node (ref "U6") (pin "27") (pinfunction "RXC/PHYAD1_27") (pintype "passive"))
    )
    (net (code "24") (name "/RGMII1_RX_CTL") (class "Default")
      (node (ref "R249") (pin "2") (pinfunction "2_2") (pintype "passive"))
      (node (ref "R252") (pin "1") (pinfunction "1_1") (pintype "passive"))
      (node (ref "U1") (pin "AE17") (pinfunction "RGMII1_RX_CTL_AE17") (pintype "passive"))
      (node (ref "U6") (pin "26") (pinfunction "RXCTL/PHYAD2_26") (pintype "passive"))
    )
    (net (code "25") (name "/RGMII1_TD0") (class "Default")
      (node (ref "R51") (pin "1") (pinfunction "1_1") (pintype "passive"))
      (node (ref "U1") (pin "AE20") (pinfunction "RGMII1_TD0_AE20") (pintype "passive"))
    )
    (net (code "26") (name "/RGMII1_TD1") (class "Default")
      (node (ref "R52") (pin "1") (pinfunction "1_1") (pintype "passive"))
      (node (ref "U1") (pin "AD20") (pinfunction "RGMII1_TD1_AD20") (pintype "passive"))
    )
    (net (code "27") (name "/RGMII1_TD2") (class "Default")
      (node (ref "R57") (pin "1") (pinfunction "1_1") (pintype "passive"))
      (node (ref "U1") (pin "AE18") (pinfunction "RGMII1_TD2_AE18") (pintype "passive"))
    )
    (net (code "28") (name "/RGMII1_TD3") (class "Default")
      (node (ref "R58") (pin "1") (pinfunction "1_1") (pintype "passive"))
      (node (ref "U1") (pin "AD18") (pinfunction "RGMII1_TD3_AD18") (pintype "passive"))
    )
    (net (code "29") (name "/RGMII1_TXC") (class "Default")
      (node (ref "R49") (pin "1") (pinfunction "1_1") (pintype "passive"))
      (node (ref "U1") (pin "AE19") (pinfunction "RGMII1_TXC_AE19") (pintype "passive"))
    )
    (net (code "30") (name "/RGMII1_TX_CTL") (class "Default")
      (node (ref "R50") (pin "1") (pinfunction "1_1") (pintype "passive"))
      (node (ref "U1") (pin "AD19") (pinfunction "RGMII1_TX_CTL_AD19") (pintype "passive"))
    )
    (net (code "31") (name "/RSET") (class "Default")
      (node (ref "R33") (pin "1") (pinfunction "1_1") (pintype "passive"))
      (node (ref "U6") (pin "39") (pinfunction "RSET_39") (pintype "passive"))
    )
    (net (code "32") (name "/TXC") (class "Default")
      (node (ref "R49") (pin "2") (pinfunction "2_2") (pintype "passive"))
      (node (ref "U6") (pin "20") (pinfunction "TXC_20") (pintype "passive"))
    )
    (net (code "33") (name "/TXCTL") (class "Default")
      (node (ref "R50") (pin "2") (pinfunction "2_2") (pintype "passive"))
      (node (ref "U6") (pin "19") (pinfunction "TXCTL_19") (pintype "passive"))
    )
    (net (code "34") (name "/TXD0") (class "Default")
      (node (ref "R51") (pin "2") (pinfunction "2_2") (pintype "passive"))
      (node (ref "U6") (pin "18") (pinfunction "TXD0_18") (pintype "passive"))
    )
    (net (code "35") (name "/TXD1") (class "Default")
      (node (ref "R52") (pin "2") (pinfunction "2_2") (pintype "passive"))
      (node (ref "U6") (pin "17") (pinfunction "TXD1_17") (pintype "passive"))
    )
    (net (code "36") (name "/TXD2") (class "Default")
      (node (ref "R57") (pin "2") (pinfunction "2_2") (pintype "passive"))
      (node (ref "U6") (pin "16") (pinfunction "TXD2_16") (pintype "passive"))
    )
    (net (code "37") (name "/TXD3") (class "Default")
      (node (ref "R58") (pin "2") (pinfunction "2_2") (pintype "passive"))
      (node (ref "U6") (pin "15") (pinfunction "TXD3_15") (pintype "passive"))
    )
    (net (code "38") (name "/XTAL_IN") (class "Default")
      (node (ref "C88") (pin "1") (pinfunction "1_1") (pintype "passive"))
      (node (ref "R277") (pin "1") (pinfunction "1_1") (pintype "passive"))
      (node (ref "U6") (pin "36") (pinfunction "XTAL_IN_36") (pintype "passive"))
      (node (ref "Y2") (pin "1") (pinfunction "1_1") (pintype "passive"))
    )
    (net (code "39") (name "/XTAL_OUT") (class "Default")
      (node (ref "R229") (pin "2") (pinfunction "2_2") (pintype "passive"))
      (node (ref "R248") (pin "2") (pinfunction "2_2") (pintype "passive"))
      (node (ref "U6") (pin "37") (pinfunction "XTAL_OUT/EXT_CLK_37") (pintype "passive"))
    )
    (net (code "40") (name "GBE_INTn") (class "Default")
      (node (ref "Q14") (pin "2") (pinfunction "S_2") (pintype "passive"))
      (node (ref "R259") (pin "2") (pinfunction "2_2") (pintype "passive"))
    )
    (net (code "41") (name "GBE_RSTn") (class "Default")
      (node (ref "D32") (pin "2") (pinfunction "C_2") (pintype "passive"))
    )
    (net (code "42") (name "GND") (class "Default")
      (node (ref "C107") (pin "2") (pinfunction "2_2") (pintype "passive"))
      (node (ref "C108") (pin "2") (pinfunction "2_2") (pintype "passive"))
      (node (ref "C294") (pin "2") (pinfunction "2_2") (pintype "passive"))
      (node (ref "C295") (pin "2") (pinfunction "2_2") (pintype "passive"))
      (node (ref "C296") (pin "2") (pinfunction "2_2") (pintype "passive"))
      (node (ref "C297") (pin "2") (pinfunction "2_2") (pintype "passive"))
      (node (ref "C298") (pin "2") (pinfunction "2_2") (pintype "passive"))
      (node (ref "C299") (pin "2") (pinfunction "2_2") (pintype "passive"))
      (node (ref "C300") (pin "2") (pinfunction "2_2") (pintype "passive"))
      (node (ref "C88") (pin "2") (pinfunction "2_2") (pintype "passive"))
      (node (ref "C89") (pin "2") (pinfunction "2_2") (pintype "passive"))
      (node (ref "C90") (pin "1") (pinfunction "1_1") (pintype "passive"))
      (node (ref "C91") (pin "2") (pinfunction "2_2") (pintype "passive"))
      (node (ref "C92") (pin "2") (pinfunction "2_2") (pintype "passive"))
      (node (ref "C93") (pin "2") (pinfunction "2_2") (pintype "passive"))
      (node (ref "C94") (pin "2") (pinfunction "2_2") (pintype "passive"))
      (node (ref "C95") (pin "2") (pinfunction "2_2") (pintype "passive"))
      (node (ref "D1") (pin "3") (pinfunction "GND1_3") (pintype "input"))
      (node (ref "D1") (pin "8") (pinfunction "GND1_8") (pintype "input"))
      (node (ref "D2") (pin "3") (pinfunction "GND1_3") (pintype "input"))
      (node (ref "D2") (pin "8") (pinfunction "GND1_8") (pintype "input"))
      (node (ref "J24") (pin "1") (pinfunction "CT5_1") (pintype "passive"))
      (node (ref "R249") (pin "1") (pinfunction "1_1") (pintype "passive"))
      (node (ref "R253") (pin "1") (pinfunction "1_1") (pintype "passive"))
      (node (ref "R277") (pin "2") (pinfunction "2_2") (pintype "passive"))
      (node (ref "R308") (pin "1") (pinfunction "1_1") (pintype "passive"))
      (node (ref "R310") (pin "1") (pinfunction "1_1") (pintype "passive"))
      (node (ref "R33") (pin "2") (pinfunction "2_2") (pintype "passive"))
      (node (ref "R41") (pin "1") (pinfunction "1_1") (pintype "passive"))
      (node (ref "R43") (pin "1") (pinfunction "1_1") (pintype "passive"))
      (node (ref "R45") (pin "1") (pinfunction "1_1") (pintype "passive"))
      (node (ref "R47") (pin "1") (pinfunction "1_1") (pintype "passive"))
      (node (ref "R61") (pin "1") (pinfunction "1_1") (pintype "passive"))
      (node (ref "U6") (pin "41") (pinfunction "EGND_41") (pintype "passive"))
      (node (ref "Y2") (pin "2") (pinfunction "GND_2") (pintype "power_in"))
      (node (ref "Y2") (pin "4") (pinfunction "GND_4") (pintype "power_in"))
    )
    (net (code "43") (name "GND_EARTH") (class "Default")
      (node (ref "J24") (pin "15") (pinfunction "SHIELD1_15") (pintype "passive"))
      (node (ref "J24") (pin "16") (pinfunction "SHIELD0_16") (pintype "passive"))
    )
    (net (code "44") (name "MCU_OBSCLK0") (class "Default")
      (node (ref "R229") (pin "1") (pinfunction "1_1") (pintype "passive"))
    )
    (net (code "45") (name "MDIO0_MDC") (class "Default")
      (node (ref "U6") (pin "13") (pinfunction "MDC_13") (pintype "passive"))
    )
    (net (code "46") (name "MDIO0_MDIO") (class "Default")
      (node (ref "R263") (pin "2") (pinfunction "2_2") (pintype "passive"))
      (node (ref "U6") (pin "14") (pinfunction "MDIO_14") (pintype "passive"))
    )
    (net (code "47") (name "Net-(C89-Pad1)") (class "Default")
      (node (ref "C89") (pin "1") (pinfunction "1_1") (pintype "passive"))
      (node (ref "R248") (pin "1") (pinfunction "1_1") (pintype "passive"))
      (node (ref "Y2") (pin "3") (pinfunction "3_3") (pintype "passive"))
    )
    (net (code "48") (name "Net-(D32-A)") (class "Default")
      (node (ref "D32") (pin "1") (pinfunction "A_1") (pintype "passive"))
      (node (ref "D33") (pin "1") (pinfunction "A_1") (pintype "passive"))
      (node (ref "D54") (pin "1") (pinfunction "A_1") (pintype "passive"))
      (node (ref "Q13") (pin "2") (pinfunction "S_2") (pintype "passive"))
      (node (ref "R36") (pin "2") (pinfunction "2_2") (pintype "passive"))
    )
    (net (code "49") (name "Net-(J24-GAOC)") (class "Default")
      (node (ref "J24") (pin "11") (pinfunction "GAOC_11") (pintype "passive"))
      (node (ref "R35") (pin "2") (pinfunction "2_2") (pintype "passive"))
      (node (ref "R39") (pin "2") (pinfunction "2_2") (pintype "passive"))
    )
    (net (code "50") (name "Net-(J24-GCOA)") (class "Default")
      (node (ref "J24") (pin "12") (pinfunction "GCOA_12") (pintype "passive"))
      (node (ref "R164") (pin "2") (pinfunction "2_2") (pintype "passive"))
      (node (ref "R40") (pin "2") (pinfunction "2_2") (pintype "passive"))
    )
    (net (code "51") (name "Net-(J24-YELA)") (class "Default")
      (node (ref "J24") (pin "14") (pinfunction "YELA_14") (pintype "passive"))
      (node (ref "R34") (pin "2") (pinfunction "2_2") (pintype "passive"))
    )
    (net (code "52") (name "Net-(J24-YELC)") (class "Default")
      (node (ref "J24") (pin "13") (pinfunction "YELC_13") (pintype "passive"))
      (node (ref "R165") (pin "2") (pinfunction "2_2") (pintype "passive"))
    )
    (net (code "53") (name "PHY_DVDD3V3") (class "Default")
      (node (ref "C91") (pin "1") (pinfunction "1_1") (pintype "passive"))
      (node (ref "C92") (pin "1") (pinfunction "1_1") (pintype "passive"))
      (node (ref "FB29") (pin "2") (pinfunction "2_2") (pintype "passive"))
      (node (ref "R164") (pin "1") (pinfunction "1_1") (pintype "passive"))
      (node (ref "R262") (pin "1") (pinfunction "1_1") (pintype "passive"))
      (node (ref "R283") (pin "2") (pinfunction "2_2") (pintype "passive"))
      (node (ref "R309") (pin "2") (pinfunction "2_2") (pintype "passive"))
      (node (ref "R311") (pin "2") (pinfunction "2_2") (pintype "passive"))
      (node (ref "R34") (pin "1") (pinfunction "1_1") (pintype "passive"))
      (node (ref "R37") (pin "1") (pinfunction "1_1") (pintype "passive"))
      (node (ref "R39") (pin "1") (pinfunction "1_1") (pintype "passive"))
      (node (ref "U6") (pin "29") (pinfunction "DVDD33_29_29") (pintype "power_in"))
    )
    (net (code "54") (name "PHY_VDD1V0") (class "Default")
      (node (ref "C299") (pin "1") (pinfunction "1_1") (pintype "passive"))
      (node (ref "C300") (pin "1") (pinfunction "1_1") (pintype "passive"))
      (node (ref "FB30") (pin "2") (pinfunction "2_2") (pintype "passive"))
      (node (ref "FB31") (pin "1") (pinfunction "1_1") (pintype "passive"))
      (node (ref "L19") (pin "2") (pinfunction "2_2") (pintype "passive"))
    )
    (net (code "55") (name "PHY_VDDIO") (class "Default")
      (node (ref "C107") (pin "1") (pinfunction "1_1") (pintype "passive"))
      (node (ref "C95") (pin "1") (pinfunction "1_1") (pintype "passive"))
      (node (ref "R252") (pin "2") (pinfunction "2_2") (pintype "passive"))
      (node (ref "R32") (pin "1") (pinfunction "1_1") (pintype "passive"))
      (node (ref "R42") (pin "2") (pinfunction "2_2") (pintype "passive"))
      (node (ref "R44") (pin "2") (pinfunction "2_2") (pintype "passive"))
      (node (ref "R46") (pin "2") (pinfunction "2_2") (pintype "passive"))
      (node (ref "R48") (pin "2") (pinfunction "2_2") (pintype "passive"))
      (node (ref "R62") (pin "2") (pinfunction "2_2") (pintype "passive"))
      (node (ref "U6") (pin "28") (pinfunction "DVDD_RG_28") (pintype "power_in"))
    )
    (net (code "56") (name "PORz_OUT") (class "Default")
      (node (ref "D33") (pin "2") (pinfunction "C_2") (pintype "passive"))
    )
    (net (code "57") (name "RESETSTATz") (class "Default")
      (node (ref "D54") (pin "2") (pinfunction "C_2") (pintype "passive"))
    )
    (net (code "58") (name "VDD_1V8") (class "Default")
      (node (ref "Q13") (pin "1") (pinfunction "G_1") (pintype "input"))
      (node (ref "Q14") (pin "1") (pinfunction "G_1") (pintype "input"))
      (node (ref "R259") (pin "1") (pinfunction "1_1") (pintype "passive"))
      (node (ref "R263") (pin "1") (pinfunction "1_1") (pintype "passive"))
      (node (ref "R32") (pin "2") (pinfunction "2_2") (pintype "passive"))
      (node (ref "R36") (pin "1") (pinfunction "1_1") (pintype "passive"))
    )
    (net (code "59") (name "VDD_3V3") (class "Default")
      (node (ref "FB29") (pin "1") (pinfunction "1_1") (pintype "passive"))
      (node (ref "FB32") (pin "2") (pinfunction "2_2") (pintype "passive"))
    )
    (net (code "60") (name "unconnected-(J24-NC-Pad10)") (class "Default")
      (node (ref "J24") (pin "10") (pinfunction "NC_10") (pintype "passive+no_connect"))
    )
  )
)
